# 02_ULTRASONIC_PGA460.net
KiCad netlist of a schematic drawn in Altium Designer
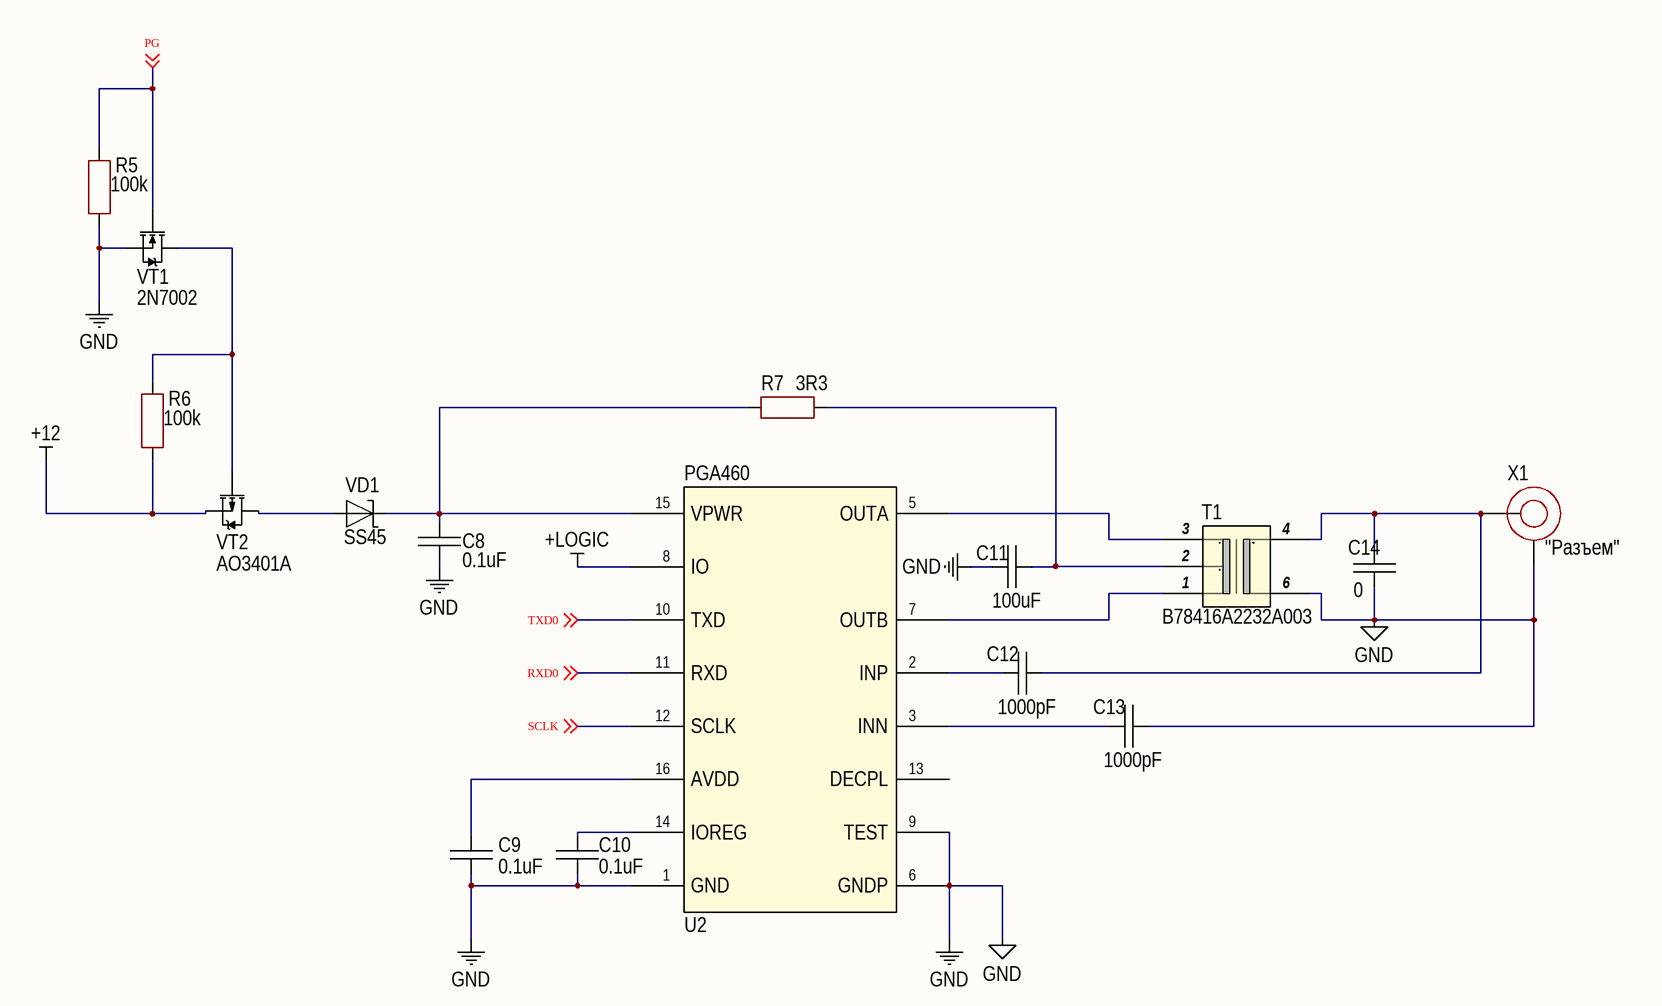
[diagram p0: 02_ULTRASONIC_PGA460.SchDoc]

(export (version "E")
  (design (tool "Eeschema 10.0.6"))
  (components
    (comp (ref "C8")
      (value "0.1uF")
      (footprint "CAP: 0603")
      (fields
        (field (name "MANUFACTURER") "Yageo")
        (field (name "PARTNUMBER") "CC0603KRX7R7BB104")
        (field (name "VALUEMANUFACTURERPARTNUMBER") "Ceramic capacitor, 0.1uF, X7R, ±10%, 16V, 0603, -55...+125°C")
      )
      (libsource (lib "capacitor") (part "Ceramic_0603"))
    )
    (comp (ref "C9")
      (value "0.1uF")
      (footprint "CAP: 0603")
      (fields
        (field (name "MANUFACTURER") "Yageo")
        (field (name "PARTNUMBER") "CC0603KRX7R7BB104")
        (field (name "VALUEMANUFACTURERPARTNUMBER") "Ceramic capacitor, 0.1uF, X7R, ±10%, 16V, 0603, -55...+125°C")
      )
      (libsource (lib "capacitor") (part "Ceramic_0603"))
    )
    (comp (ref "C10")
      (value "0.1uF")
      (footprint "CAP: 0603")
      (fields
        (field (name "MANUFACTURER") "Yageo")
        (field (name "PARTNUMBER") "CC0603KRX7R7BB104")
        (field (name "VALUEMANUFACTURERPARTNUMBER") "Ceramic capacitor, 0.1uF, X7R, ±10%, 16V, 0603, -55...+125°C")
      )
      (libsource (lib "capacitor") (part "Ceramic_0603"))
    )
    (comp (ref "C11")
      (value "100uF")
      (footprint "CAP: 1206")
      (fields
        (field (name "MANUFACTURER") "Yageo")
        (field (name "PARTNUMBER") "CC1206KRX7R9BB104")
        (field (name "VALUEMANUFACTURERPARTNUMBER") "Ceramic capacitor, 100uF, X7R, ±10%, 50V, 1206, -55...+125°C")
      )
      (libsource (lib "capacitor") (part "Ceramic_1206"))
    )
    (comp (ref "C12")
      (value "1000pF")
      (footprint "CAP: 0805")
      (fields
        (field (name "MANUFACTURER") "Yageo")
        (field (name "PARTNUMBER") "CC0805KRX7R7BB104")
        (field (name "VALUEMANUFACTURERPARTNUMBER") "Ceramic capacitor, 1000pF, NP0, ±5%, 500V, 0805, -55...+125°C")
      )
      (libsource (lib "capacitor") (part "Ceramic_0805"))
    )
    (comp (ref "C13")
      (value "1000pF")
      (footprint "CAP: 0805")
      (fields
        (field (name "MANUFACTURER") "Yageo")
        (field (name "PARTNUMBER") "CC0805KRX7R7BB104")
        (field (name "VALUEMANUFACTURERPARTNUMBER") "Ceramic capacitor, 1000pF, NP0, ±5%, 500V, 0805, -55...+125°C")
      )
      (libsource (lib "capacitor") (part "Ceramic_0805"))
    )
    (comp (ref "C14")
      (value "0")
      (footprint "CAP: 0805")
      (fields
        (field (name "MANUFACTURER") "Yageo")
        (field (name "PARTNUMBER") "CC0805KRX7R7BB104")
        (field (name "VALUEMANUFACTURERPARTNUMBER") "Ceramic capacitor, 0, NP0, ±5%, 16V, 0805, -55...+125°C")
      )
      (libsource (lib "capacitor") (part "Ceramic_0805"))
    )
    (comp (ref "R5")
      (value "100k")
      (footprint "RES: 0603")
      (fields
        (field (name "MANUFACTURER") "Yageo")
        (field (name "PARTNUMBER") "RC0603JR-07100RL")
        (field (name "VALUEMANUFACTURERPARTNUMBER") "Resistor film, 100k, ±5%, 0603, 0.1W, -55...+125°C")
      )
      (libsource (lib "resistor") (part "Resistor_0603"))
    )
    (comp (ref "R6")
      (value "100k")
      (footprint "RES: 0603")
      (fields
        (field (name "MANUFACTURER") "Yageo")
        (field (name "PARTNUMBER") "RC0603JR-07100RL")
        (field (name "VALUEMANUFACTURERPARTNUMBER") "Resistor film, 100k, ±5%, 0603, 0.1W, -55...+125°C")
      )
      (libsource (lib "resistor") (part "Resistor_0603"))
    )
    (comp (ref "R7")
      (value "3R3")
      (footprint "RES: 2010")
      (fields
        (field (name "MANUFACTURER") "Yageo")
        (field (name "PARTNUMBER") "RC2010JK-07100RL")
        (field (name "VALUEMANUFACTURERPARTNUMBER") "Resistor film, 3R3, ±5%, 2010, 0.75W, -55...+125°C")
      )
      (libsource (lib "resistor") (part "Resistor_2010"))
    )
    (comp (ref "T1")
      (value "B78416A2232A003")
      (footprint "B78416_TDK")
      (description "Description")
      (fields (field (name "COPYRIGHT") "Copyright (C) 2025 Ultra Librarian. All rights reserved."))
      (libsource (lib "B78416A2232A003") (part "B78416A2232A003"))
    )
    (comp (ref "U2") (value "PGA460") (footprint "16-TSSOP") (libsource (lib "MyLib") (part "PGA460")))
    (comp (ref "VD1")
      (value "~")
      (footprint "DIODE: SMC")
      (fields
        (field (name "MANUFACTURER") "Diodes Incorporated")
        (field (name "VALUEMANUFACTURERPARTNUMBER") "Schottky diode, 80V, 500mA, 1V, 15pF, SOD-123, -55...+150°C")
        (field (name "VOLTAGE") "80V")
        (field (name "PARTNUMBER") "SS45")
      )
      (libsource (lib "diode") (part "Schottky_single"))
    )
    (comp (ref "VT1")
      (value "~")
      (footprint "SOT23")
      (fields
        (field (name "MANUFACTURER") "Infineon Technologies")
        (field (name "VALUEMANUFACTURERPARTNUMBER") "MOSFET N-channel transistor, 80V, 7A, 9.1nC, 2.5W, 34mOhm, 756pF, 8-TDSON, -55...+150°C")
        (field (name "PARTNUMBER") "2N7002")
      )
      (libsource (lib "transistor") (part "MOSFET_N_132"))
    )
    (comp (ref "VT2")
      (value "~")
      (footprint "SOT23")
      (fields
        (field (name "MANUFACTURER") "Infineon Technologies")
        (field (name "VALUEMANUFACTURERPARTNUMBER") "MOSFET P-channel transistor, 20V, 2.6A, 2.9nC, 2.5W, 135mOhm, 220pF, SOT-23, -55...+150°C")
        (field (name "PARTNUMBER") "AO3401A")
      )
      (libsource (lib "transistor") (part "MOSFET_P_132"))
    )
    (comp (ref "X1")
      (value "~")
      (footprint "CON: SMA")
      (fields
        (field (name "MANUFACTURER") "TE Connectivity")
        (field (name "VALUEMANUFACTURERPARTNUMBER") "Connector SMA, 50 Ohm, 3GHz")
        (field (name "PARTNUMBER") "5-1814832-1")
        (field (name "COMMENTTEXT") "\"Разъем\"")
      )
      (libsource (lib "connector") (part "Connector_SMA"))
    )
  )
  (nets
    (net (code "1") (name "+12") (class "Default")
      (node (ref "R6") (pin "1") (pinfunction "1_1") (pintype "passive"))
      (node (ref "VT2") (pin "2") (pinfunction "S_2") (pintype "passive"))
    )
    (net (code "2") (name "+LOGIC") (class "Default")
      (node (ref "U2") (pin "8") (pinfunction "IO_8") (pintype "passive"))
    )
    (net (code "3") (name "GND") (class "Default")
      (node (ref "C10") (pin "1") (pinfunction "1_1") (pintype "passive"))
      (node (ref "C11") (pin "2") (pinfunction "2_2") (pintype "passive"))
      (node (ref "C13") (pin "1") (pinfunction "1_1") (pintype "passive"))
      (node (ref "C14") (pin "2") (pinfunction "2_2") (pintype "passive"))
      (node (ref "C8") (pin "1") (pinfunction "1_1") (pintype "passive"))
      (node (ref "C9") (pin "1") (pinfunction "1_1") (pintype "passive"))
      (node (ref "R5") (pin "1") (pinfunction "1_1") (pintype "passive"))
      (node (ref "T1") (pin "6") (pinfunction "6_6") (pintype "passive"))
      (node (ref "U2") (pin "1") (pinfunction "GND_1") (pintype "passive"))
      (node (ref "U2") (pin "6") (pinfunction "GNDP_6") (pintype "passive"))
      (node (ref "U2") (pin "9") (pinfunction "TEST_9") (pintype "passive"))
      (node (ref "VT1") (pin "2") (pinfunction "S_2") (pintype "passive"))
      (node (ref "X1") (pin "2") (pinfunction "2_2") (pintype "passive"))
    )
    (net (code "4") (name "Net-(C11-Pad1)") (class "Default")
      (node (ref "C11") (pin "1") (pinfunction "1_1") (pintype "passive"))
      (node (ref "R7") (pin "2") (pinfunction "2_2") (pintype "passive"))
      (node (ref "T1") (pin "2") (pinfunction "2_2") (pintype "passive"))
    )
    (net (code "5") (name "Net-(C12-Pad1)") (class "Default")
      (node (ref "C12") (pin "1") (pinfunction "1_1") (pintype "passive"))
      (node (ref "C14") (pin "1") (pinfunction "1_1") (pintype "passive"))
      (node (ref "T1") (pin "4") (pinfunction "4_4") (pintype "passive"))
      (node (ref "X1") (pin "1") (pinfunction "1_1") (pintype "passive"))
    )
    (net (code "6") (name "Net-(U2-AVDD)") (class "Default")
      (node (ref "C9") (pin "2") (pinfunction "2_2") (pintype "passive"))
      (node (ref "U2") (pin "16") (pinfunction "AVDD_16") (pintype "passive"))
    )
    (net (code "7") (name "Net-(U2-INN)") (class "Default")
      (node (ref "C13") (pin "2") (pinfunction "2_2") (pintype "passive"))
      (node (ref "U2") (pin "3") (pinfunction "INN_3") (pintype "passive"))
    )
    (net (code "8") (name "Net-(U2-INP)") (class "Default")
      (node (ref "C12") (pin "2") (pinfunction "2_2") (pintype "passive"))
      (node (ref "U2") (pin "2") (pinfunction "INP_2") (pintype "passive"))
    )
    (net (code "9") (name "Net-(U2-IOREG)") (class "Default")
      (node (ref "C10") (pin "2") (pinfunction "2_2") (pintype "passive"))
      (node (ref "U2") (pin "14") (pinfunction "IOREG_14") (pintype "passive"))
    )
    (net (code "10") (name "Net-(U2-OUTA)") (class "Default")
      (node (ref "T1") (pin "3") (pinfunction "3_3") (pintype "passive"))
      (node (ref "U2") (pin "5") (pinfunction "OUTA_5") (pintype "passive"))
    )
    (net (code "11") (name "Net-(U2-OUTB)") (class "Default")
      (node (ref "T1") (pin "1") (pinfunction "1_1") (pintype "passive"))
      (node (ref "U2") (pin "7") (pinfunction "OUTB_7") (pintype "passive"))
    )
    (net (code "12") (name "Net-(U2-VPWR)") (class "Default")
      (node (ref "C8") (pin "2") (pinfunction "2_2") (pintype "passive"))
      (node (ref "R7") (pin "1") (pinfunction "1_1") (pintype "passive"))
      (node (ref "U2") (pin "15") (pinfunction "VPWR_15") (pintype "passive"))
      (node (ref "VD1") (pin "2") (pinfunction "2_2") (pintype "passive"))
    )
    (net (code "13") (name "Net-(VT1-D)") (class "Default")
      (node (ref "R6") (pin "2") (pinfunction "2_2") (pintype "passive"))
      (node (ref "VT1") (pin "3") (pinfunction "D_3") (pintype "passive"))
      (node (ref "VT2") (pin "1") (pinfunction "G_1") (pintype "passive"))
    )
    (net (code "14") (name "Net-(VT2-D)") (class "Default")
      (node (ref "VD1") (pin "1") (pinfunction "1_1") (pintype "passive"))
      (node (ref "VT2") (pin "3") (pinfunction "D_3") (pintype "passive"))
    )
    (net (code "15") (name "PG") (class "Default")
      (node (ref "R5") (pin "2") (pinfunction "2_2") (pintype "passive"))
      (node (ref "VT1") (pin "1") (pinfunction "G_1") (pintype "passive"))
    )
    (net (code "16") (name "RXD0") (class "Default")
      (node (ref "U2") (pin "11") (pinfunction "RXD_11") (pintype "passive"))
    )
    (net (code "17") (name "SCLK") (class "Default")
      (node (ref "U2") (pin "12") (pinfunction "SCLK_12") (pintype "passive"))
    )
    (net (code "18") (name "TXD0") (class "Default")
      (node (ref "U2") (pin "10") (pinfunction "TXD_10") (pintype "passive"))
    )
    (net (code "19") (name "unconnected-(U2-DECPL-Pad13)") (class "Default")
      (node (ref "U2") (pin "13") (pinfunction "DECPL_13") (pintype "passive"))
    )
  )
)
